# eagle-TSL2591.net
KiCad netlist of a schematic drawn in EAGLE
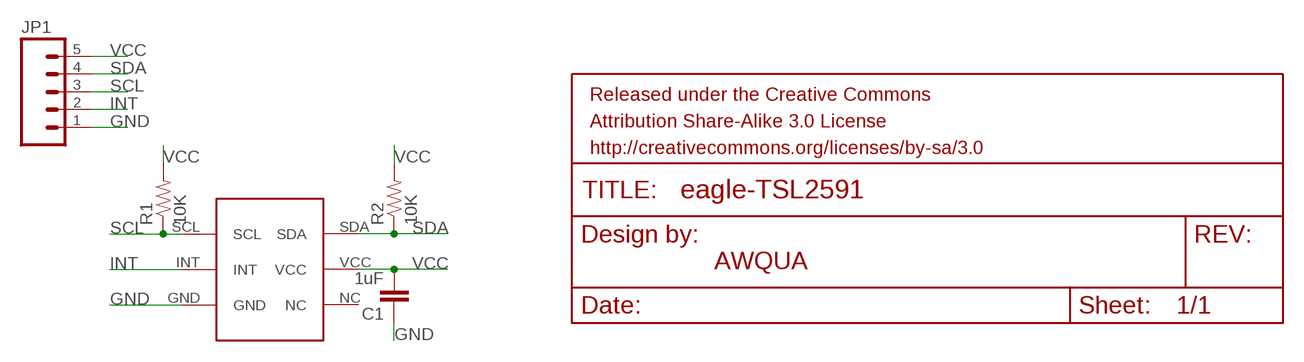
[diagram p0: schematic, sheet 1]

(export (version "E")
  (design (tool "Eeschema 10.0.6"))
  (components
    (comp (ref "C1")
      (value "1uF")
      (footprint "eagle-import:0603-CAP")
      (libsource (lib "eagle-import") (part "CAP0603-CAP"))
    )
    (comp (ref "FRAME1")
      (value "FRAME-LETTER")
      (footprint "eagle-import:CREATIVE_COMMONS")
      (libsource (lib "eagle-import") (part "FRAME-LETTER"))
    )
    (comp (ref "JP1")
      (value "M05NO_SILK")
      (footprint "eagle-import:1X05_NO_SILK")
      (libsource (lib "eagle-import") (part "M05NO_SILK"))
    )
    (comp (ref "R1")
      (value "10K")
      (footprint "eagle-import:0603-RES")
      (libsource (lib "eagle-import") (part "RESISTOR0603-RES"))
    )
    (comp (ref "R2")
      (value "10K")
      (footprint "eagle-import:0603-RES")
      (libsource (lib "eagle-import") (part "RESISTOR0603-RES"))
    )
    (comp (ref "U$1")
      (value "TSL2591")
      (footprint "eagle-import:TSL2591")
      (libsource (lib "eagle-import") (part "TSL2591"))
    )
  )
  (nets
    (net (code "1") (name "/GND") (class "Default")
      (node (ref "C1") (pin "1") (pinfunction "1_1") (pintype "passive"))
      (node (ref "JP1") (pin "1") (pinfunction "1_1") (pintype "passive"))
      (node (ref "U$1") (pin "GND") (pinfunction "GND_GND") (pintype "bidirectional"))
    )
    (net (code "2") (name "/INT") (class "Default")
      (node (ref "JP1") (pin "2") (pinfunction "2_2") (pintype "passive"))
      (node (ref "U$1") (pin "INT") (pinfunction "INT_INT") (pintype "bidirectional"))
    )
    (net (code "3") (name "/SCL") (class "Default")
      (node (ref "JP1") (pin "3") (pinfunction "3_3") (pintype "passive"))
      (node (ref "R1") (pin "1") (pinfunction "1_1") (pintype "passive"))
      (node (ref "U$1") (pin "SCL") (pinfunction "SCL_SCL") (pintype "bidirectional"))
    )
    (net (code "4") (name "/SDA") (class "Default")
      (node (ref "JP1") (pin "4") (pinfunction "4_4") (pintype "passive"))
      (node (ref "R2") (pin "1") (pinfunction "1_1") (pintype "passive"))
      (node (ref "U$1") (pin "SDA") (pinfunction "SDA_SDA") (pintype "bidirectional"))
    )
    (net (code "5") (name "/VCC") (class "Default")
      (node (ref "C1") (pin "2") (pinfunction "2_2") (pintype "passive"))
      (node (ref "JP1") (pin "5") (pinfunction "5_5") (pintype "passive"))
      (node (ref "R1") (pin "2") (pinfunction "2_2") (pintype "passive"))
      (node (ref "R2") (pin "2") (pinfunction "2_2") (pintype "passive"))
      (node (ref "U$1") (pin "VCC") (pinfunction "VCC_VCC") (pintype "bidirectional"))
    )
    (net (code "6") (name "unconnected-(U$1-PadNC)") (class "Default")
      (node (ref "U$1") (pin "NC") (pinfunction "NC_NC") (pintype "bidirectional"))
    )
  )
)
